# Microphone.net
KiCad netlist of a schematic drawn in EAGLE
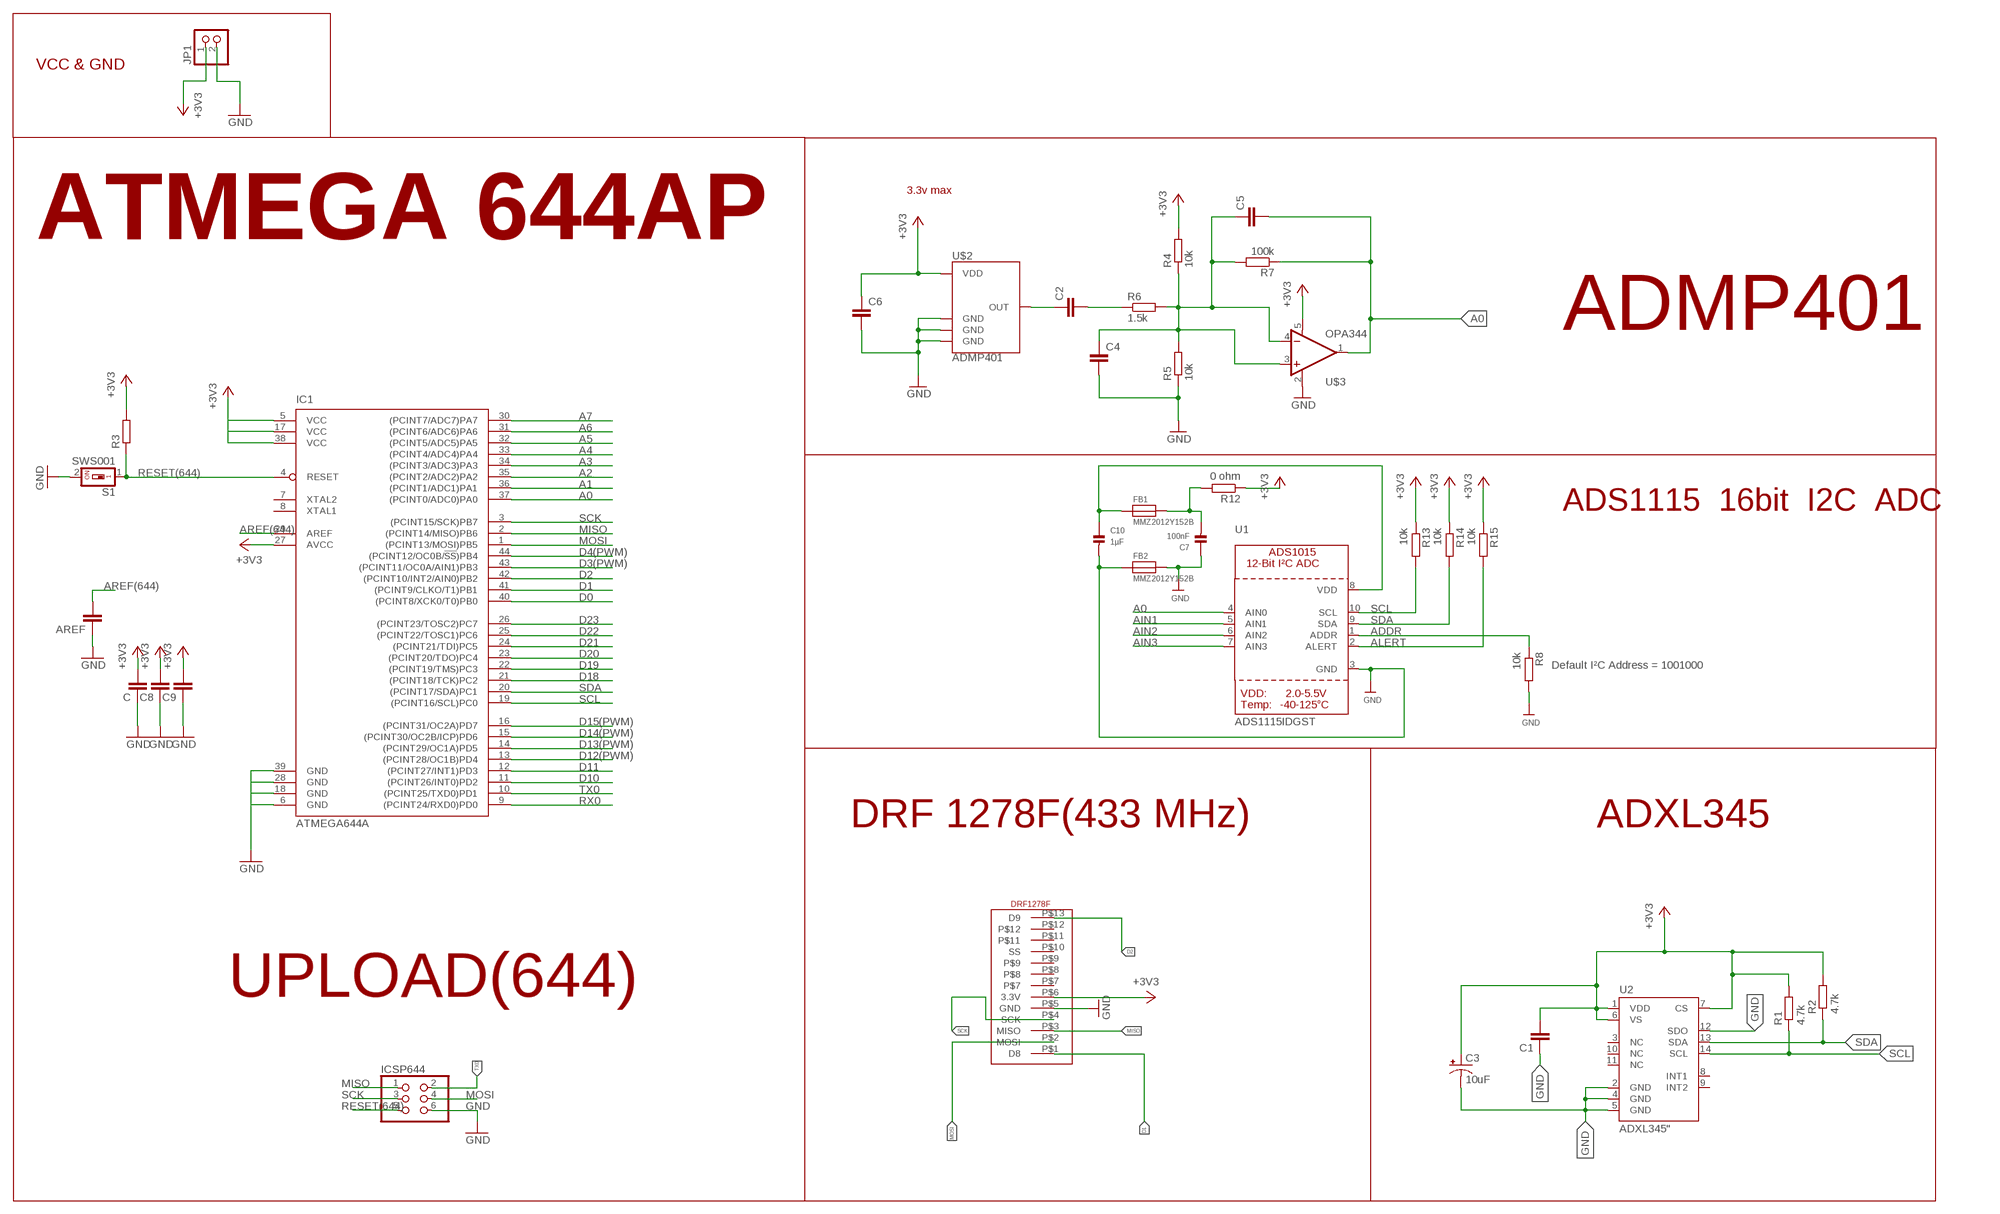
[diagram p0: schematic, sheet 1]

(export (version "E")
  (design (tool "Eeschema 10.0.6"))
  (components
    (comp (ref "AREF")
      (value "100nF")
      (footprint "eagle-import:C0805")
      (libsource (lib "eagle-import") (part "C-EUC0805"))
    )
    (comp (ref "C")
      (value "22 uF")
      (footprint "eagle-import:C0805")
      (libsource (lib "eagle-import") (part "C-EUC0805"))
    )
    (comp (ref "C1")
      (value "0.1uF")
      (footprint "eagle-import:C0805")
      (libsource (lib "eagle-import") (part "C-EUC0805"))
    )
    (comp (ref "C2")
      (value "4.7uF")
      (footprint "eagle-import:C0805")
      (libsource (lib "eagle-import") (part "C-EUC0805"))
    )
    (comp (ref "C3")
      (value "10uF")
      (footprint "eagle-import:EIA3216")
      (libsource (lib "eagle-import") (part "CAP_POL1206"))
    )
    (comp (ref "C4")
      (value "1uF")
      (footprint "eagle-import:C0805")
      (libsource (lib "eagle-import") (part "C-EUC0805"))
    )
    (comp (ref "C5")
      (value "100pF")
      (footprint "eagle-import:C0805")
      (libsource (lib "eagle-import") (part "C-EUC0805"))
    )
    (comp (ref "C6")
      (value "0.1uF")
      (footprint "eagle-import:C0805")
      (libsource (lib "eagle-import") (part "C-EUC0805"))
    )
    (comp (ref "C7")
      (value "100nF")
      (footprint "eagle-import:0805")
      (libsource (lib "eagle-import") (part "CAP_CERAMIC0805"))
    )
    (comp (ref "C8")
      (value "100nF")
      (footprint "eagle-import:C0805")
      (libsource (lib "eagle-import") (part "C-EUC0805"))
    )
    (comp (ref "C9")
      (value "100nF")
      (footprint "eagle-import:C0805")
      (libsource (lib "eagle-import") (part "C-EUC0805"))
    )
    (comp (ref "C10")
      (value "1µF")
      (footprint "eagle-import:0805")
      (libsource (lib "eagle-import") (part "CAP_CERAMIC0805"))
    )
    (comp (ref "FB1")
      (value "MMZ2012Y152B")
      (footprint "eagle-import:0805")
      (libsource (lib "eagle-import") (part "FERRITE0805"))
    )
    (comp (ref "FB2")
      (value "MMZ2012Y152B")
      (footprint "eagle-import:0805")
      (libsource (lib "eagle-import") (part "FERRITE0805"))
    )
    (comp (ref "IC1")
      (value "ATMEGA644A")
      (footprint "eagle-import:TQFP44")
      (fields (field (name "MPN") "ATMEGA644PV-10AU"))
      (libsource (lib "eagle-import") (part "ATMEGA644A"))
    )
    (comp (ref "ICSP644")
      (value "PINHD-2X3")
      (footprint "eagle-import:2X03")
      (libsource (lib "eagle-import") (part "PINHD-2X3"))
    )
    (comp (ref "JP1")
      (value "PINHD-1X2")
      (footprint "eagle-import:1X02")
      (libsource (lib "eagle-import") (part "PINHD-1X2"))
    )
    (comp (ref "R1")
      (value "4.7k")
      (footprint "eagle-import:R0805")
      (libsource (lib "eagle-import") (part "resistor_R-EU_R0805"))
    )
    (comp (ref "R2")
      (value "4.7k")
      (footprint "eagle-import:R0805")
      (libsource (lib "eagle-import") (part "resistor_R-EU_R0805"))
    )
    (comp (ref "R3")
      (value "R-EU_R0805")
      (footprint "eagle-import:R0805")
      (libsource (lib "eagle-import") (part "resistor_R-EU_R0805"))
    )
    (comp (ref "R4")
      (value "10k")
      (footprint "eagle-import:R0805")
      (libsource (lib "eagle-import") (part "R-EU_R0805"))
    )
    (comp (ref "R5")
      (value "10k")
      (footprint "eagle-import:R0805")
      (libsource (lib "eagle-import") (part "R-EU_R0805"))
    )
    (comp (ref "R6")
      (value "1.5k")
      (footprint "eagle-import:R0805")
      (libsource (lib "eagle-import") (part "R-EU_R0805"))
    )
    (comp (ref "R7")
      (value "100k")
      (footprint "eagle-import:R0805")
      (libsource (lib "eagle-import") (part "R-EU_R0805"))
    )
    (comp (ref "R8")
      (value "10k")
      (footprint "eagle-import:R0805")
      (libsource (lib "eagle-import") (part "resistor_R-EU_R0805"))
    )
    (comp (ref "R12")
      (value "0 ohm")
      (footprint "eagle-import:R0805")
      (libsource (lib "eagle-import") (part "resistor_R-EU_R0805"))
    )
    (comp (ref "R13")
      (value "10k")
      (footprint "eagle-import:R0805")
      (libsource (lib "eagle-import") (part "resistor_R-EU_R0805"))
    )
    (comp (ref "R14")
      (value "10k")
      (footprint "eagle-import:R0805")
      (libsource (lib "eagle-import") (part "resistor_R-EU_R0805"))
    )
    (comp (ref "R15")
      (value "10k")
      (footprint "eagle-import:R0805")
      (libsource (lib "eagle-import") (part "resistor_R-EU_R0805"))
    )
    (comp (ref "S1")
      (value "SWS001")
      (footprint "eagle-import:SMS-001")
      (libsource (lib "eagle-import") (part "SWS001"))
    )
    (comp (ref "U$1")
      (value "DRF1278F")
      (footprint "eagle-import:DIP13")
      (libsource (lib "eagle-import") (part "DRF1278F"))
    )
    (comp (ref "U$2")
      (value "ADMP401")
      (footprint "eagle-import:ADMP401")
      (libsource (lib "eagle-import") (part "ADMP401"))
    )
    (comp (ref "U$3")
      (value "OPA344")
      (footprint "eagle-import:SOT23-5")
      (libsource (lib "eagle-import") (part "OPA344"))
    )
    (comp (ref "U1")
      (value "ADS1115IDGST")
      (footprint "eagle-import:MSOP10")
      (libsource (lib "eagle-import") (part "ADC_ADS1015"))
    )
    (comp (ref "U2")
      (value "ADXL345\"")
      (footprint "eagle-import:ADXL3451_1")
      (libsource (lib "eagle-import") (part "ADXL345{dblquote}"))
    )
  )
  (nets
    (net (code "1") (name "+3V3") (class "Default")
      (node (ref "C") (pin "2") (pinfunction "2_2") (pintype "passive"))
      (node (ref "C1") (pin "2") (pinfunction "2_2") (pintype "passive"))
      (node (ref "C3") (pin "A") (pinfunction "+_A") (pintype "passive"))
      (node (ref "C6") (pin "1") (pinfunction "1_1") (pintype "passive"))
      (node (ref "C8") (pin "2") (pinfunction "2_2") (pintype "passive"))
      (node (ref "C9") (pin "2") (pinfunction "2_2") (pintype "passive"))
      (node (ref "IC1") (pin "17") (pinfunction "VCC_17") (pintype "power_in"))
      (node (ref "IC1") (pin "27") (pinfunction "AVCC_27") (pintype "power_in"))
      (node (ref "IC1") (pin "38") (pinfunction "VCC_38") (pintype "power_in"))
      (node (ref "IC1") (pin "5") (pinfunction "VCC_5") (pintype "power_in"))
      (node (ref "JP1") (pin "1") (pinfunction "1_1") (pintype "passive"))
      (node (ref "R1") (pin "2") (pinfunction "2_2") (pintype "passive"))
      (node (ref "R12") (pin "1") (pinfunction "1_1") (pintype "passive"))
      (node (ref "R13") (pin "1") (pinfunction "1_1") (pintype "passive"))
      (node (ref "R14") (pin "1") (pinfunction "1_1") (pintype "passive"))
      (node (ref "R15") (pin "1") (pinfunction "1_1") (pintype "passive"))
      (node (ref "R2") (pin "2") (pinfunction "2_2") (pintype "passive"))
      (node (ref "R3") (pin "2") (pinfunction "2_2") (pintype "passive"))
      (node (ref "R4") (pin "2") (pinfunction "2_2") (pintype "passive"))
      (node (ref "U$1") (pin "P$6") (pinfunction "3.3V_P$6") (pintype "bidirectional"))
      (node (ref "U$2") (pin "5") (pinfunction "VDD_5") (pintype "bidirectional"))
      (node (ref "U$3") (pin "5") (pinfunction "V+_5") (pintype "power_in"))
      (node (ref "U2") (pin "1") (pinfunction "VDD_1") (pintype "bidirectional"))
      (node (ref "U2") (pin "6") (pinfunction "VS_6") (pintype "bidirectional"))
      (node (ref "U2") (pin "7") (pinfunction "CS_7") (pintype "bidirectional"))
    )
    (net (code "2") (name "/A1") (class "Default")
      (node (ref "IC1") (pin "36") (pinfunction "(PCINT1/ADC1)PA1_36") (pintype "bidirectional"))
    )
    (net (code "3") (name "/A2") (class "Default")
      (node (ref "IC1") (pin "35") (pinfunction "(PCINT2/ADC2)PA2_35") (pintype "bidirectional"))
    )
    (net (code "4") (name "/A3") (class "Default")
      (node (ref "IC1") (pin "34") (pinfunction "(PCINT3/ADC3)PA3_34") (pintype "bidirectional"))
    )
    (net (code "5") (name "/A4") (class "Default")
      (node (ref "IC1") (pin "33") (pinfunction "(PCINT4/ADC4)PA4_33") (pintype "bidirectional"))
    )
    (net (code "6") (name "/A5") (class "Default")
      (node (ref "IC1") (pin "32") (pinfunction "(PCINT5/ADC5)PA5_32") (pintype "bidirectional"))
    )
    (net (code "7") (name "/A6") (class "Default")
      (node (ref "IC1") (pin "31") (pinfunction "(PCINT6/ADC6)PA6_31") (pintype "bidirectional"))
    )
    (net (code "8") (name "/A7") (class "Default")
      (node (ref "IC1") (pin "30") (pinfunction "(PCINT7/ADC7)PA7_30") (pintype "bidirectional"))
    )
    (net (code "9") (name "/ADDR") (class "Default")
      (node (ref "R8") (pin "1") (pinfunction "1_1") (pintype "passive"))
      (node (ref "U1") (pin "1") (pinfunction "ADDR_1") (pintype "bidirectional"))
    )
    (net (code "10") (name "/AIN1") (class "Default")
      (node (ref "U1") (pin "5") (pinfunction "AIN1_5") (pintype "bidirectional"))
    )
    (net (code "11") (name "/AIN2") (class "Default")
      (node (ref "U1") (pin "6") (pinfunction "AIN2_6") (pintype "bidirectional"))
    )
    (net (code "12") (name "/AIN3") (class "Default")
      (node (ref "U1") (pin "7") (pinfunction "AIN3_7") (pintype "bidirectional"))
    )
    (net (code "13") (name "/ALERT") (class "Default")
      (node (ref "R15") (pin "2") (pinfunction "2_2") (pintype "passive"))
      (node (ref "U1") (pin "2") (pinfunction "ALERT_2") (pintype "bidirectional"))
    )
    (net (code "14") (name "/AREF(644)") (class "Default")
      (node (ref "AREF") (pin "2") (pinfunction "2_2") (pintype "passive"))
      (node (ref "IC1") (pin "29") (pinfunction "AREF_29") (pintype "passive"))
    )
    (net (code "15") (name "/D0") (class "Default")
      (node (ref "IC1") (pin "40") (pinfunction "(PCINT8/XCK0/T0)PB0_40") (pintype "bidirectional"))
    )
    (net (code "16") (name "/D3(PWM)") (class "Default")
      (node (ref "IC1") (pin "43") (pinfunction "(PCINT11/OC0A/AIN1)PB3_43") (pintype "bidirectional"))
    )
    (net (code "17") (name "/D4(PWM)") (class "Default")
      (node (ref "IC1") (pin "44") (pinfunction "(PCINT12/OC0B/~{SS})PB4_44") (pintype "bidirectional"))
    )
    (net (code "18") (name "/D10") (class "Default")
      (node (ref "IC1") (pin "11") (pinfunction "(PCINT26/INT0)PD2_11") (pintype "bidirectional"))
    )
    (net (code "19") (name "/D11") (class "Default")
      (node (ref "IC1") (pin "12") (pinfunction "(PCINT27/INT1)PD3_12") (pintype "bidirectional"))
    )
    (net (code "20") (name "/D12(PWM)") (class "Default")
      (node (ref "IC1") (pin "13") (pinfunction "(PCINT28/OC1B)PD4_13") (pintype "bidirectional"))
    )
    (net (code "21") (name "/D13(PWM)") (class "Default")
      (node (ref "IC1") (pin "14") (pinfunction "(PCINT29/OC1A)PD5_14") (pintype "bidirectional"))
    )
    (net (code "22") (name "/D14(PWM)") (class "Default")
      (node (ref "IC1") (pin "15") (pinfunction "(PCINT30/OC2B/ICP)PD6_15") (pintype "bidirectional"))
    )
    (net (code "23") (name "/D15(PWM)") (class "Default")
      (node (ref "IC1") (pin "16") (pinfunction "(PCINT31/OC2A)PD7_16") (pintype "bidirectional"))
    )
    (net (code "24") (name "/D18") (class "Default")
      (node (ref "IC1") (pin "21") (pinfunction "(PCINT18/TCK)PC2_21") (pintype "output"))
    )
    (net (code "25") (name "/D19") (class "Default")
      (node (ref "IC1") (pin "22") (pinfunction "(PCINT19/TMS)PC3_22") (pintype "output"))
    )
    (net (code "26") (name "/D20") (class "Default")
      (node (ref "IC1") (pin "23") (pinfunction "(PCINT20/TDO)PC4_23") (pintype "output"))
    )
    (net (code "27") (name "/D21") (class "Default")
      (node (ref "IC1") (pin "24") (pinfunction "(PCINT21/TDI)PC5_24") (pintype "output"))
    )
    (net (code "28") (name "/D22") (class "Default")
      (node (ref "IC1") (pin "25") (pinfunction "(PCINT22/TOSC1)PC6_25") (pintype "output"))
    )
    (net (code "29") (name "/D23") (class "Default")
      (node (ref "IC1") (pin "26") (pinfunction "(PCINT23/TOSC2)PC7_26") (pintype "output"))
    )
    (net (code "30") (name "/RESET(644)") (class "Default")
      (node (ref "IC1") (pin "4") (pinfunction "RESET_4") (pintype "input"))
      (node (ref "ICSP644") (pin "5") (pinfunction "5_5") (pintype "passive"))
      (node (ref "R3") (pin "1") (pinfunction "1_1") (pintype "passive"))
      (node (ref "S1") (pin "1") (pinfunction "1_1") (pintype "passive"))
    )
    (net (code "31") (name "/RX0") (class "Default")
      (node (ref "IC1") (pin "9") (pinfunction "(PCINT24/RXD0)PD0_9") (pintype "bidirectional"))
    )
    (net (code "32") (name "A0") (class "Default")
      (node (ref "C5") (pin "2") (pinfunction "2_2") (pintype "passive"))
      (node (ref "IC1") (pin "37") (pinfunction "(PCINT0/ADC0)PA0_37") (pintype "bidirectional"))
      (node (ref "R7") (pin "1") (pinfunction "1_1") (pintype "passive"))
      (node (ref "U$3") (pin "1") (pinfunction "OUT_1") (pintype "output"))
      (node (ref "U1") (pin "4") (pinfunction "AIN0_4") (pintype "bidirectional"))
    )
    (net (code "33") (name "D1") (class "Default")
      (node (ref "IC1") (pin "41") (pinfunction "(PCINT9/CLKO/T1)PB1_41") (pintype "bidirectional"))
      (node (ref "U$1") (pin "P$1") (pinfunction "D8_P$1") (pintype "bidirectional"))
    )
    (net (code "34") (name "D2") (class "Default")
      (node (ref "IC1") (pin "42") (pinfunction "(PCINT10/INT2/AIN0)PB2_42") (pintype "bidirectional"))
      (node (ref "U$1") (pin "P$13") (pinfunction "D9_P$13") (pintype "bidirectional"))
    )
    (net (code "35") (name "GND") (class "Default")
      (node (ref "AREF") (pin "1") (pinfunction "1_1") (pintype "passive"))
      (node (ref "C") (pin "1") (pinfunction "1_1") (pintype "passive"))
      (node (ref "C1") (pin "1") (pinfunction "1_1") (pintype "passive"))
      (node (ref "C10") (pin "2") (pinfunction "P$2_2") (pintype "passive"))
      (node (ref "C3") (pin "C") (pinfunction "-_C") (pintype "passive"))
      (node (ref "C4") (pin "2") (pinfunction "2_2") (pintype "passive"))
      (node (ref "C6") (pin "2") (pinfunction "2_2") (pintype "passive"))
      (node (ref "C7") (pin "1") (pinfunction "P$1_1") (pintype "passive"))
      (node (ref "C8") (pin "1") (pinfunction "1_1") (pintype "passive"))
      (node (ref "C9") (pin "1") (pinfunction "1_1") (pintype "passive"))
      (node (ref "FB2") (pin "1") (pinfunction "P$1_1") (pintype "bidirectional"))
      (node (ref "FB2") (pin "2") (pinfunction "P$2_2") (pintype "bidirectional"))
      (node (ref "IC1") (pin "18") (pinfunction "GND_18") (pintype "power_in"))
      (node (ref "IC1") (pin "28") (pinfunction "GND_28") (pintype "power_in"))
      (node (ref "IC1") (pin "39") (pinfunction "GND_39") (pintype "power_in"))
      (node (ref "IC1") (pin "6") (pinfunction "GND_6") (pintype "power_in"))
      (node (ref "ICSP644") (pin "6") (pinfunction "6_6") (pintype "passive"))
      (node (ref "JP1") (pin "2") (pinfunction "2_2") (pintype "passive"))
      (node (ref "R5") (pin "1") (pinfunction "1_1") (pintype "passive"))
      (node (ref "R8") (pin "2") (pinfunction "2_2") (pintype "passive"))
      (node (ref "S1") (pin "2") (pinfunction "2_2") (pintype "passive"))
      (node (ref "U$1") (pin "P$5") (pinfunction "GND_P$5") (pintype "bidirectional"))
      (node (ref "U$2") (pin "2") (pinfunction "GND_2") (pintype "bidirectional"))
      (node (ref "U$2") (pin "4") (pinfunction "GND_4") (pintype "bidirectional"))
      (node (ref "U$2") (pin "6") (pinfunction "GND_6") (pintype "bidirectional"))
      (node (ref "U$3") (pin "2") (pinfunction "V-_2") (pintype "power_in"))
      (node (ref "U1") (pin "3") (pinfunction "GND_3") (pintype "bidirectional"))
      (node (ref "U2") (pin "12") (pinfunction "SDO_12") (pintype "bidirectional"))
      (node (ref "U2") (pin "2") (pinfunction "GND_2") (pintype "bidirectional"))
      (node (ref "U2") (pin "4") (pinfunction "GND_4") (pintype "bidirectional"))
      (node (ref "U2") (pin "5") (pinfunction "GND_5") (pintype "bidirectional"))
    )
    (net (code "36") (name "MISO") (class "Default")
      (node (ref "IC1") (pin "2") (pinfunction "(PCINT14/MISO)PB6_2") (pintype "bidirectional"))
      (node (ref "ICSP644") (pin "1") (pinfunction "1_1") (pintype "passive"))
      (node (ref "U$1") (pin "P$3") (pinfunction "MISO_P$3") (pintype "bidirectional"))
    )
    (net (code "37") (name "MOSI") (class "Default")
      (node (ref "IC1") (pin "1") (pinfunction "(PCINT13/MOSI)PB5_1") (pintype "bidirectional"))
      (node (ref "ICSP644") (pin "4") (pinfunction "4_4") (pintype "passive"))
      (node (ref "U$1") (pin "P$2") (pinfunction "MOSI_P$2") (pintype "bidirectional"))
    )
    (net (code "38") (name "Net-(C2-Pad2)") (class "Default")
      (node (ref "C2") (pin "2") (pinfunction "2_2") (pintype "passive"))
      (node (ref "R6") (pin "1") (pinfunction "1_1") (pintype "passive"))
    )
    (net (code "39") (name "Net-(C7-P$2)") (class "Default")
      (node (ref "C7") (pin "2") (pinfunction "P$2_2") (pintype "passive"))
      (node (ref "FB1") (pin "2") (pinfunction "P$2_2") (pintype "bidirectional"))
      (node (ref "R12") (pin "2") (pinfunction "2_2") (pintype "passive"))
    )
    (net (code "40") (name "Net-(C10-P$1)") (class "Default")
      (node (ref "C10") (pin "1") (pinfunction "P$1_1") (pintype "passive"))
      (node (ref "FB1") (pin "1") (pinfunction "P$1_1") (pintype "bidirectional"))
      (node (ref "U1") (pin "8") (pinfunction "VDD_8") (pintype "bidirectional"))
    )
    (net (code "41") (name "Net-(U$2-OUT)") (class "Default")
      (node (ref "C2") (pin "1") (pinfunction "1_1") (pintype "passive"))
      (node (ref "U$2") (pin "1") (pinfunction "OUT_1") (pintype "bidirectional"))
    )
    (net (code "42") (name "Net-(U$3-+IN)") (class "Default")
      (node (ref "C4") (pin "1") (pinfunction "1_1") (pintype "passive"))
      (node (ref "C5") (pin "1") (pinfunction "1_1") (pintype "passive"))
      (node (ref "R4") (pin "1") (pinfunction "1_1") (pintype "passive"))
      (node (ref "R5") (pin "2") (pinfunction "2_2") (pintype "passive"))
      (node (ref "R6") (pin "2") (pinfunction "2_2") (pintype "passive"))
      (node (ref "R7") (pin "2") (pinfunction "2_2") (pintype "passive"))
      (node (ref "U$3") (pin "3") (pinfunction "+IN_3") (pintype "input"))
      (node (ref "U$3") (pin "4") (pinfunction "-IN_4") (pintype "input"))
    )
    (net (code "43") (name "SCK") (class "Default")
      (node (ref "IC1") (pin "3") (pinfunction "(PCINT15/SCK)PB7_3") (pintype "bidirectional"))
      (node (ref "ICSP644") (pin "3") (pinfunction "3_3") (pintype "passive"))
      (node (ref "U$1") (pin "P$4") (pinfunction "SCK_P$4") (pintype "bidirectional"))
    )
    (net (code "44") (name "SCL") (class "Default")
      (node (ref "IC1") (pin "19") (pinfunction "(PCINT16/SCL)PC0_19") (pintype "output"))
      (node (ref "R1") (pin "1") (pinfunction "1_1") (pintype "passive"))
      (node (ref "R13") (pin "2") (pinfunction "2_2") (pintype "passive"))
      (node (ref "U1") (pin "10") (pinfunction "SCL_10") (pintype "bidirectional"))
      (node (ref "U2") (pin "14") (pinfunction "SCL_14") (pintype "bidirectional"))
    )
    (net (code "45") (name "SDA") (class "Default")
      (node (ref "IC1") (pin "20") (pinfunction "(PCINT17/SDA)PC1_20") (pintype "output"))
      (node (ref "R14") (pin "2") (pinfunction "2_2") (pintype "passive"))
      (node (ref "R2") (pin "1") (pinfunction "1_1") (pintype "passive"))
      (node (ref "U1") (pin "9") (pinfunction "SDA_9") (pintype "bidirectional"))
      (node (ref "U2") (pin "13") (pinfunction "SDA_13") (pintype "bidirectional"))
    )
    (net (code "46") (name "TX0") (class "Default")
      (node (ref "IC1") (pin "10") (pinfunction "(PCINT25/TXD0)PD1_10") (pintype "bidirectional"))
      (node (ref "ICSP644") (pin "2") (pinfunction "2_2") (pintype "passive"))
    )
    (net (code "47") (name "unconnected-(IC1-XTAL1-Pad8)") (class "Default")
      (node (ref "IC1") (pin "8") (pinfunction "XTAL1_8") (pintype "bidirectional"))
    )
    (net (code "48") (name "unconnected-(IC1-XTAL2-Pad7)") (class "Default")
      (node (ref "IC1") (pin "7") (pinfunction "XTAL2_7") (pintype "bidirectional"))
    )
    (net (code "49") (name "unconnected-(U$1-PadP$7)") (class "Default")
      (node (ref "U$1") (pin "P$7") (pinfunction "P$7_P$7") (pintype "bidirectional"))
    )
    (net (code "50") (name "unconnected-(U$1-PadP$8)") (class "Default")
      (node (ref "U$1") (pin "P$8") (pinfunction "P$8_P$8") (pintype "bidirectional"))
    )
    (net (code "51") (name "unconnected-(U$1-PadP$9)") (class "Default")
      (node (ref "U$1") (pin "P$9") (pinfunction "P$9_P$9") (pintype "bidirectional"))
    )
    (net (code "52") (name "unconnected-(U$1-PadP$11)") (class "Default")
      (node (ref "U$1") (pin "P$11") (pinfunction "P$11_P$11") (pintype "bidirectional"))
    )
    (net (code "53") (name "unconnected-(U$1-PadP$12)") (class "Default")
      (node (ref "U$1") (pin "P$12") (pinfunction "P$12_P$12") (pintype "bidirectional"))
    )
    (net (code "54") (name "unconnected-(U$1-SS-PadP$10)") (class "Default")
      (node (ref "U$1") (pin "P$10") (pinfunction "SS_P$10") (pintype "bidirectional"))
    )
    (net (code "55") (name "unconnected-(U2-INT1-Pad8)") (class "Default")
      (node (ref "U2") (pin "8") (pinfunction "INT1_8") (pintype "bidirectional"))
    )
    (net (code "56") (name "unconnected-(U2-INT2-Pad9)") (class "Default")
      (node (ref "U2") (pin "9") (pinfunction "INT2_9") (pintype "bidirectional"))
    )
    (net (code "57") (name "unconnected-(U2-NC-Pad3)") (class "Default")
      (node (ref "U2") (pin "3") (pinfunction "NC_3") (pintype "bidirectional"))
    )
    (net (code "58") (name "unconnected-(U2-NC-Pad10)") (class "Default")
      (node (ref "U2") (pin "10") (pinfunction "NC_10") (pintype "bidirectional"))
    )
    (net (code "59") (name "unconnected-(U2-NC-Pad11)") (class "Default")
      (node (ref "U2") (pin "11") (pinfunction "NC_11") (pintype "bidirectional"))
    )
  )
)
